# RTC-EEPROM.net
KiCad netlist of a schematic drawn in Altium Designer
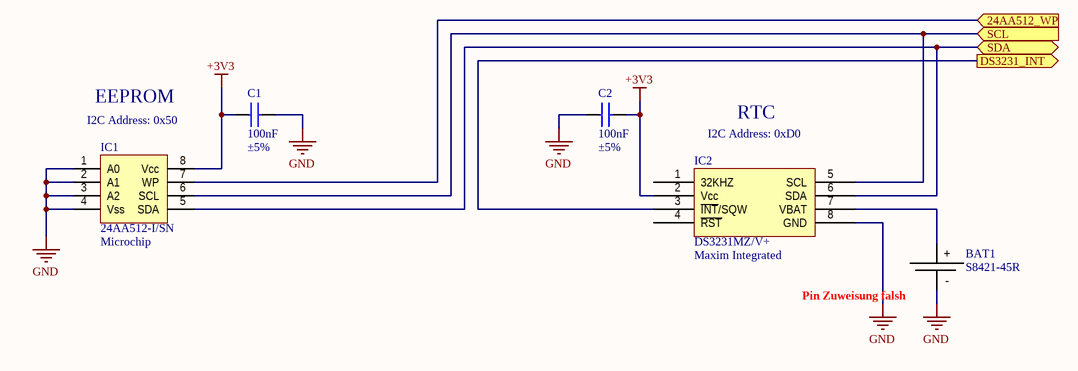
[diagram p0: RTC-EEPROM.SchDoc]

(export (version "E")
  (design (tool "Eeschema 10.0.6"))
  (components
    (comp (ref "BAT1")
      (value "S8421-45R")
      (footprint "S8421-45R")
      (description "HOLDER BATT COIN CR2032/20MM")
      (fields (field (name "MANUFACTURER") "Harwin Inc."))
      (libsource (lib "BAT_COIN") (part "S8421-45R"))
    )
    (comp (ref "C1")
      (value "C0603C104J4RACTU")
      (footprint "C0603")
      (description "CAP CER 100NF 16V 5% X7R 0603")
      (fields
        (field (name "MANUFACTURER") "Kemet")
        (field (name "KAPAZITÄT") "100nF")
        (field (name "TOLERANZ") "±5%")
      )
      (libsource (lib "CAP") (part "C0603C104J4RACTU"))
    )
    (comp (ref "C2")
      (value "C0603C104J4RACTU")
      (footprint "C0603")
      (description "CAP CER 100NF 16V 5% X7R 0603")
      (fields
        (field (name "MANUFACTURER") "Kemet")
        (field (name "KAPAZITÄT") "100nF")
        (field (name "TOLERANZ") "±5%")
      )
      (libsource (lib "CAP") (part "C0603C104J4RACTU"))
    )
    (comp (ref "IC1")
      (value "24AA512-I/SN")
      (footprint "SOIC-8")
      (description "IC EEPROM 512KBIT 400KHZ 8SOIC")
      (fields (field (name "MANUFACTURER") "Microchip"))
      (libsource (lib "EEPROM_Microchip") (part "24AA512-I/SN"))
    )
    (comp (ref "IC2")
      (value "DS3231MZ/V+")
      (footprint "SOIC-8")
      (description "IC RTC CLK/CALENDAR I2C 8-SOIC")
      (fields (field (name "MANUFACTURER") "Maxim Integrated"))
      (libsource (lib "RTC_Maxim") (part "DS3231MZ/V+"))
    )
  )
  (nets
    (net (code "1") (name "+3V3") (class "Default")
      (node (ref "C1") (pin "1") (pinfunction "1_1") (pintype "passive"))
      (node (ref "C2") (pin "2") (pinfunction "2_2") (pintype "passive"))
      (node (ref "IC1") (pin "8") (pinfunction "Vcc_8") (pintype "passive"))
      (node (ref "IC2") (pin "2") (pinfunction "Vcc_2") (pintype "passive"))
    )
    (net (code "2") (name "/24AA512_WP") (class "Default")
      (node (ref "IC1") (pin "7") (pinfunction "WP_7") (pintype "passive"))
    )
    (net (code "3") (name "/DS3231_INT") (class "Default")
      (node (ref "IC2") (pin "3") (pinfunction "~{INT}/SQW_3") (pintype "passive"))
    )
    (net (code "4") (name "/SCL") (class "Default")
      (node (ref "IC1") (pin "6") (pinfunction "SCL_6") (pintype "passive"))
      (node (ref "IC2") (pin "5") (pinfunction "SCL_5") (pintype "passive"))
    )
    (net (code "5") (name "/SDA") (class "Default")
      (node (ref "IC1") (pin "5") (pinfunction "SDA_5") (pintype "passive"))
      (node (ref "IC2") (pin "6") (pinfunction "SDA_6") (pintype "passive"))
    )
    (net (code "6") (name "GND") (class "Default")
      (node (ref "BAT1") (pin "2") (pinfunction "2_2") (pintype "passive"))
      (node (ref "C1") (pin "2") (pinfunction "2_2") (pintype "passive"))
      (node (ref "C2") (pin "1") (pinfunction "1_1") (pintype "passive"))
      (node (ref "IC1") (pin "1") (pinfunction "A0_1") (pintype "passive"))
      (node (ref "IC1") (pin "2") (pinfunction "A1_2") (pintype "passive"))
      (node (ref "IC1") (pin "3") (pinfunction "A2_3") (pintype "passive"))
      (node (ref "IC1") (pin "4") (pinfunction "Vss_4") (pintype "passive"))
      (node (ref "IC2") (pin "8") (pinfunction "GND_8") (pintype "passive"))
    )
    (net (code "7") (name "Net-(IC2-VBAT)") (class "Default")
      (node (ref "BAT1") (pin "1") (pinfunction "1_1") (pintype "passive"))
      (node (ref "IC2") (pin "7") (pinfunction "VBAT_7") (pintype "passive"))
    )
    (net (code "8") (name "unconnected-(IC2-32KHZ-Pad1)") (class "Default")
      (node (ref "IC2") (pin "1") (pinfunction "32KHZ_1") (pintype "passive"))
    )
    (net (code "9") (name "unconnected-(IC2-~{RST}-Pad4)") (class "Default")
      (node (ref "IC2") (pin "4") (pinfunction "~{RST}_4") (pintype "passive"))
    )
  )
)
